# easyeda_flashinglights.net
KiCad netlist of a schematic drawn in EasyEDA
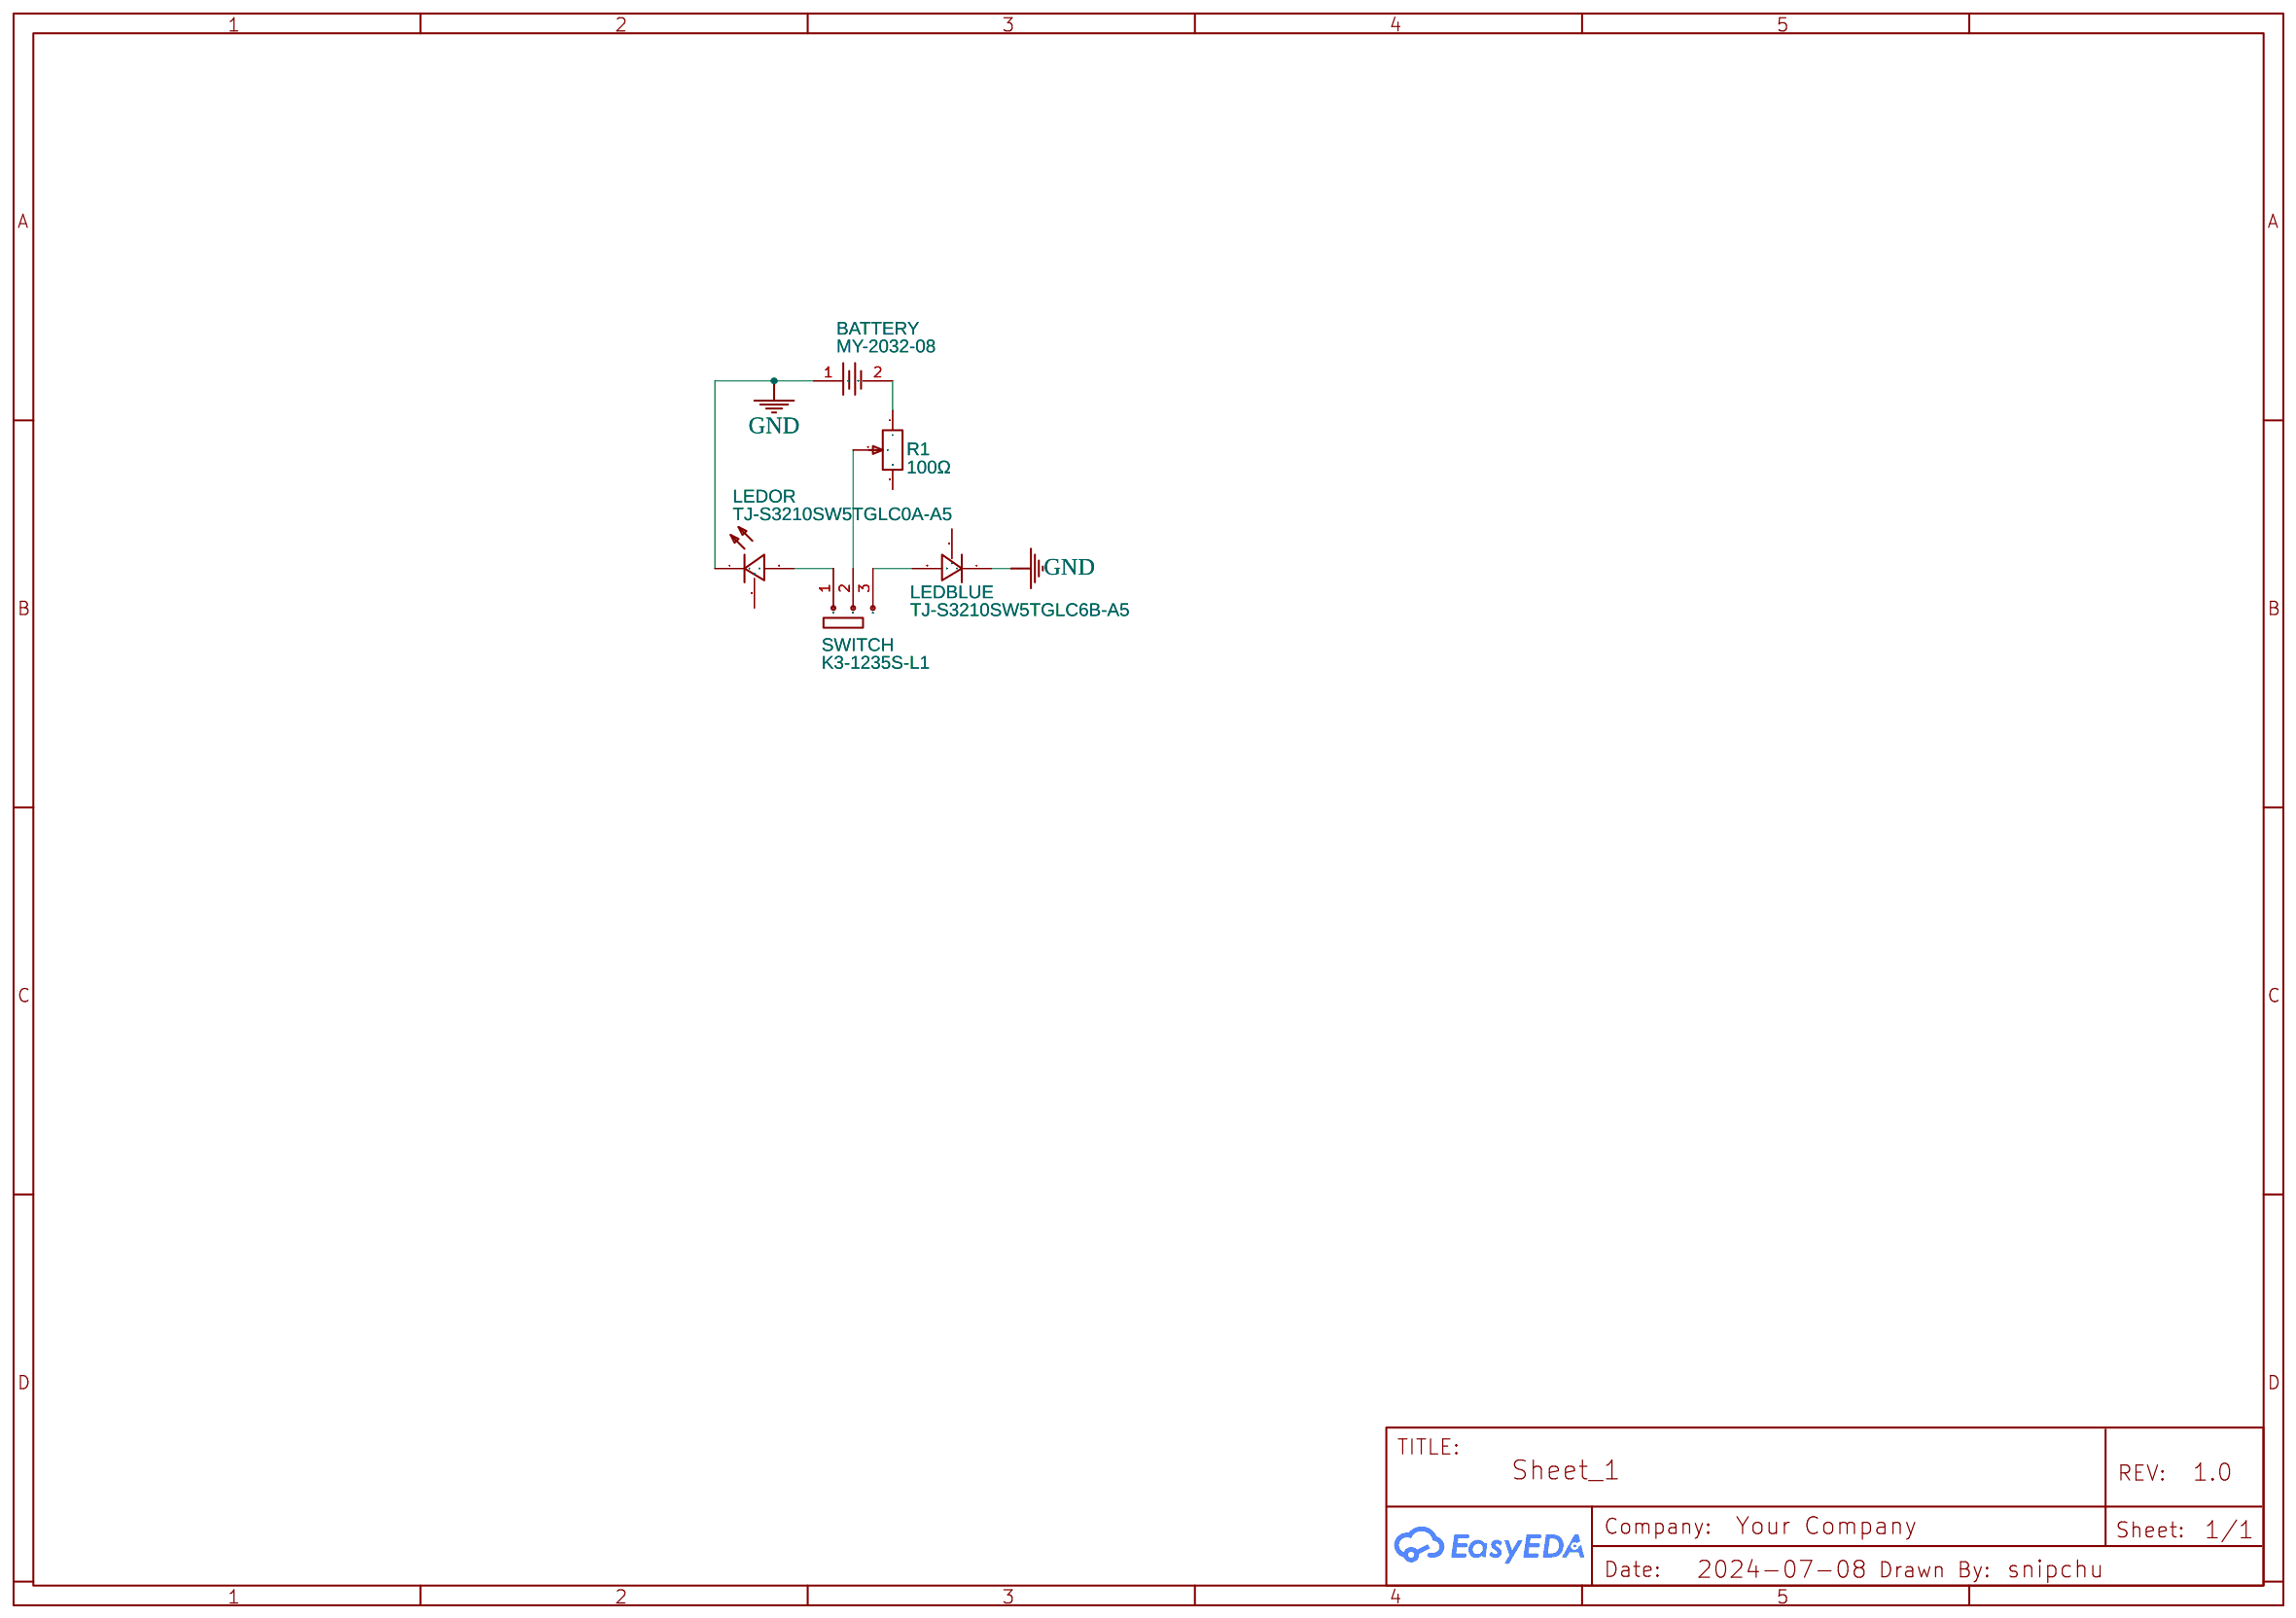
[diagram p0: schematic sheet]

(export (version "E")
  (design (tool "Eeschema 10.0.6"))
  (components
    (comp (ref "BATTERY")
      (value "MY-2032-08")
      (fields (field (name "Manufacturer") "MYOUNG(美阳)"))
      (libsource (lib "") (part "MY-2032-08"))
    )
    (comp (ref "LEDBLUE")
      (value "TJ-S3210SW5TGLC6B-A5")
      (fields (field (name "Manufacturer") "TOGIALED(统佳)"))
      (libsource (lib "") (part "TJ-S3210SW5TGLC6B-A5"))
    )
    (comp (ref "LEDOR")
      (value "TJ-S3210SW5TGLC0A-A5")
      (fields (field (name "Manufacturer") "TOGIALED(统佳)"))
      (libsource (lib "") (part "TJ-S3210SW5TGLC0A-A5"))
    )
    (comp (ref "R1")
      (value "100Ω")
      (fields (field (name "Manufacturer Part") "G43AT-B101") (field (name "Manufacturer") "TOCOS"))
      (libsource (lib "") (part "G43AT-B101"))
    )
    (comp (ref "SWITCH")
      (value "K3-1235S-L1")
      (fields (field (name "Manufacturer") "韩国韩荣"))
      (libsource (lib "") (part "K3-1235S-L1"))
    )
  )
  (nets
    (net (code "1") (name "GND") (class "Default")
      (node (ref "BATTERY") (pin "1") (pinfunction "1_1") (pintype "input"))
      (node (ref "LEDBLUE") (pin "1") (pinfunction "1_1") (pintype "unspecified"))
      (node (ref "LEDOR") (pin "1") (pinfunction "1_1") (pintype "unspecified"))
    )
    (net (code "2") (name "Net-(BATTERY-Pad2)") (class "Default")
      (node (ref "BATTERY") (pin "2") (pinfunction "2_2") (pintype "input"))
      (node (ref "R1") (pin "1") (pinfunction "1_1") (pintype "input"))
    )
    (net (code "3") (name "Net-(LEDBLUE-Pad2)") (class "Default")
      (node (ref "LEDBLUE") (pin "2") (pinfunction "2_2") (pintype "unspecified"))
      (node (ref "SWITCH") (pin "3") (pinfunction "3_3") (pintype "unspecified"))
    )
    (net (code "4") (name "Net-(LEDOR-Pad2)") (class "Default")
      (node (ref "LEDOR") (pin "2") (pinfunction "2_2") (pintype "unspecified"))
      (node (ref "SWITCH") (pin "1") (pinfunction "1_1") (pintype "unspecified"))
    )
    (net (code "5") (name "Net-(R1-Pad2)") (class "Default")
      (node (ref "R1") (pin "2") (pinfunction "2_2") (pintype "input"))
      (node (ref "SWITCH") (pin "2") (pinfunction "2_2") (pintype "unspecified"))
    )
    (net (code "6") (name "unconnected-(LEDBLUE-Pad3)") (class "Default")
      (node (ref "LEDBLUE") (pin "3") (pinfunction "3_3") (pintype "unspecified"))
    )
    (net (code "7") (name "unconnected-(LEDOR-Pad3)") (class "Default")
      (node (ref "LEDOR") (pin "3") (pinfunction "3_3") (pintype "unspecified"))
    )
    (net (code "8") (name "unconnected-(R1-Pad3)") (class "Default")
      (node (ref "R1") (pin "3") (pinfunction "3_3") (pintype "input"))
    )
  )
)
